# Box_Electronics_v25.net
KiCad netlist of a schematic drawn in EAGLE
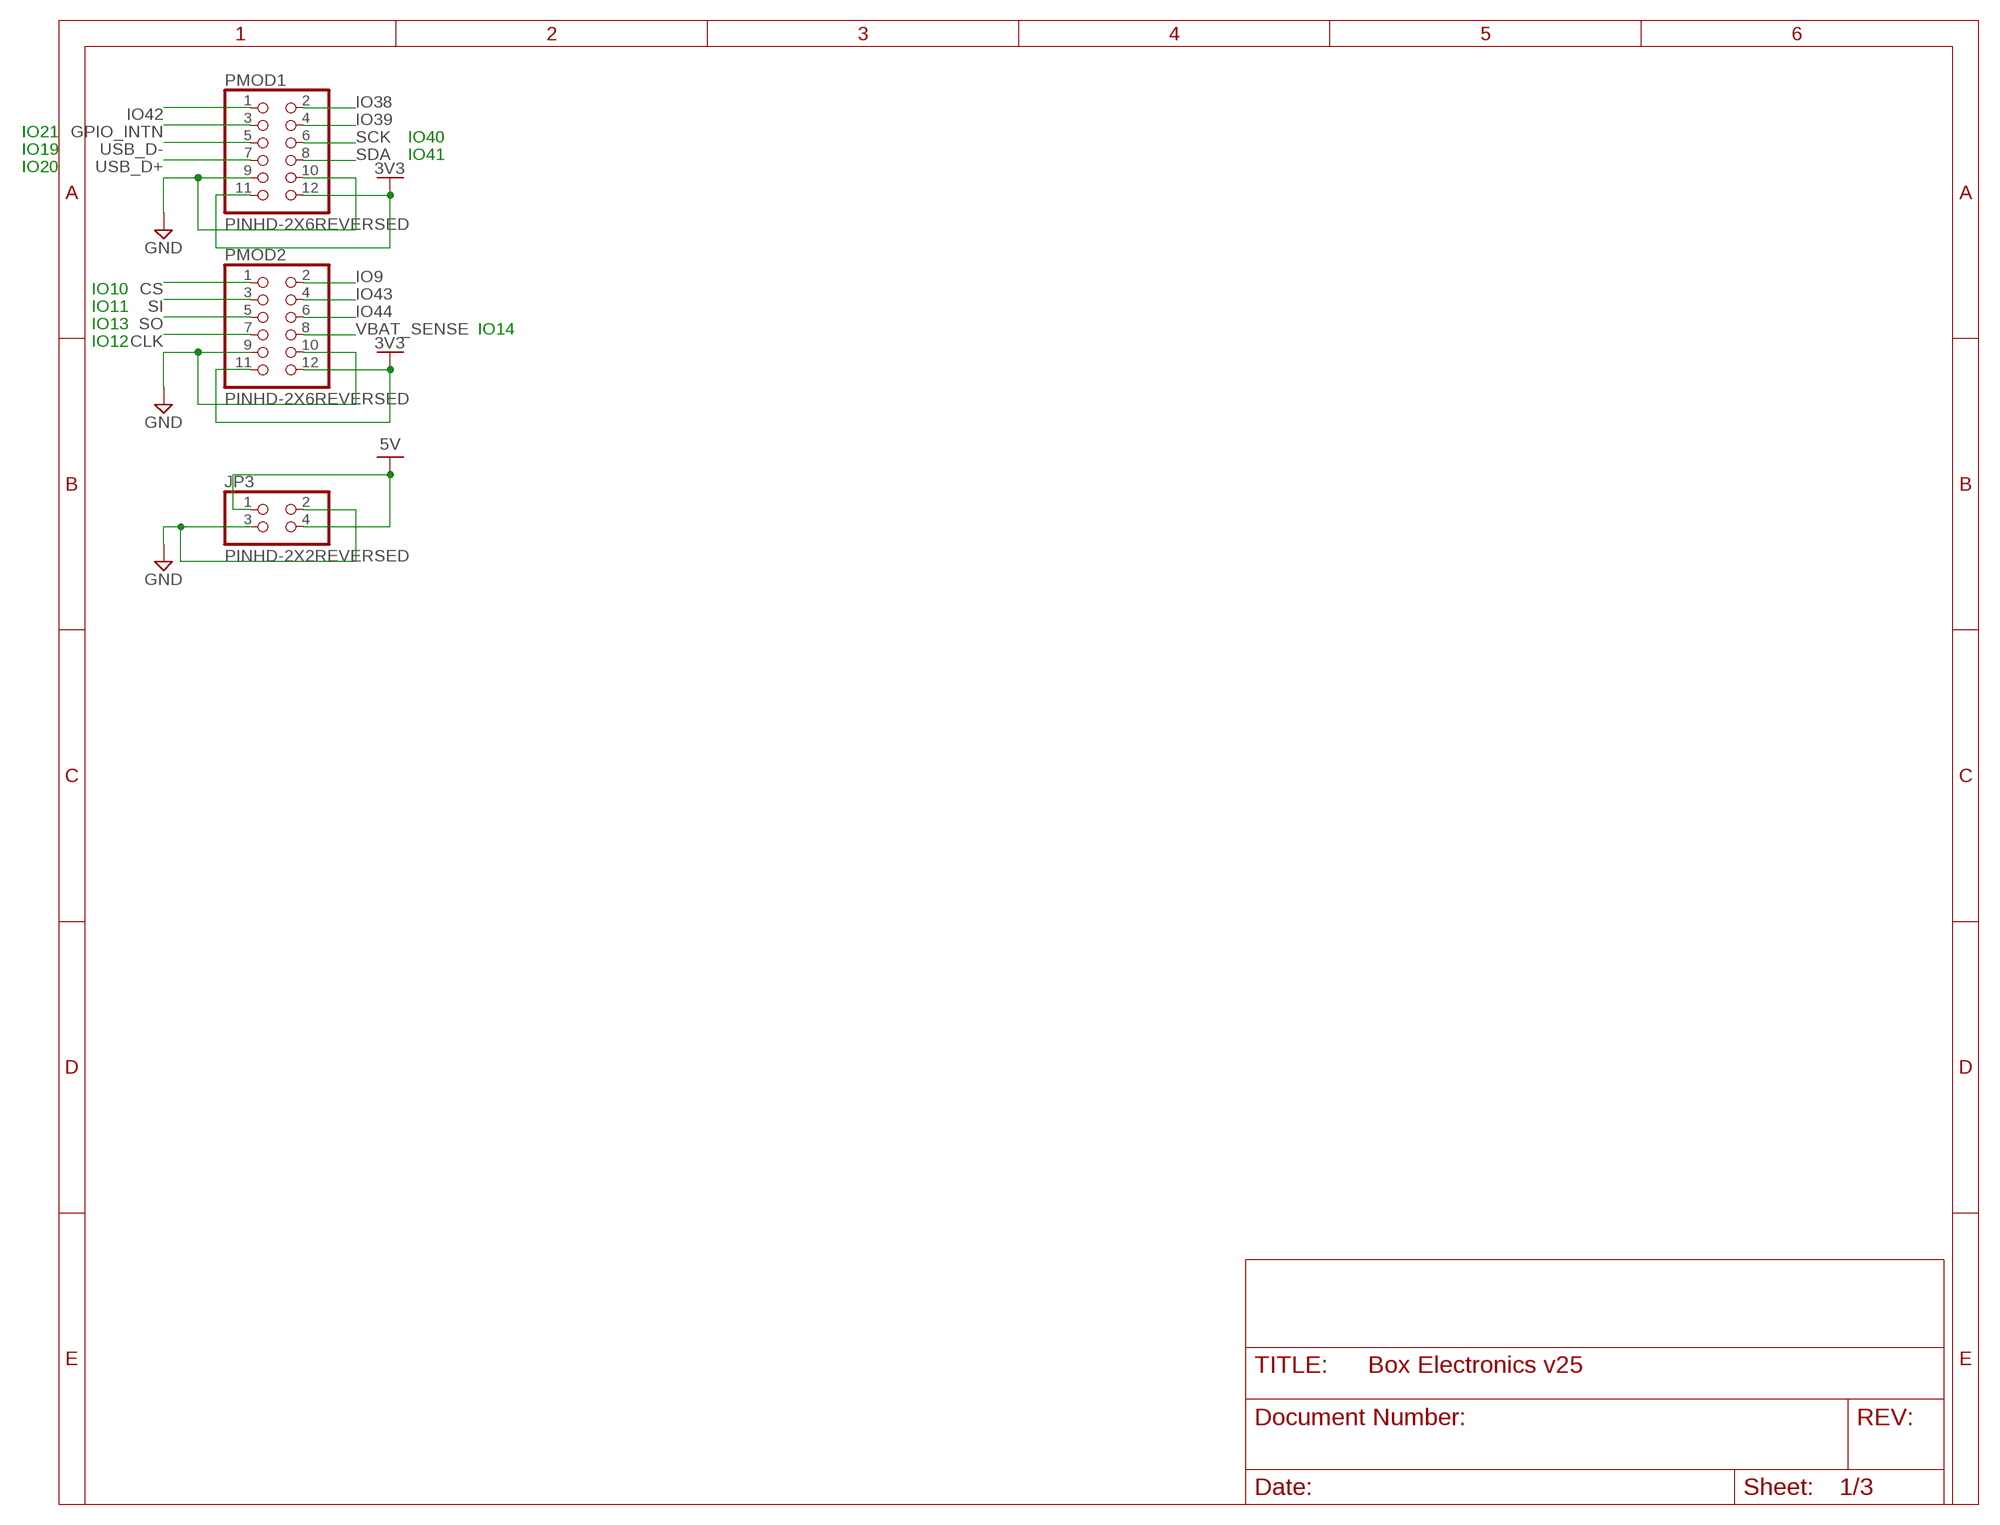
[diagram p0: schematic, sheet 1]
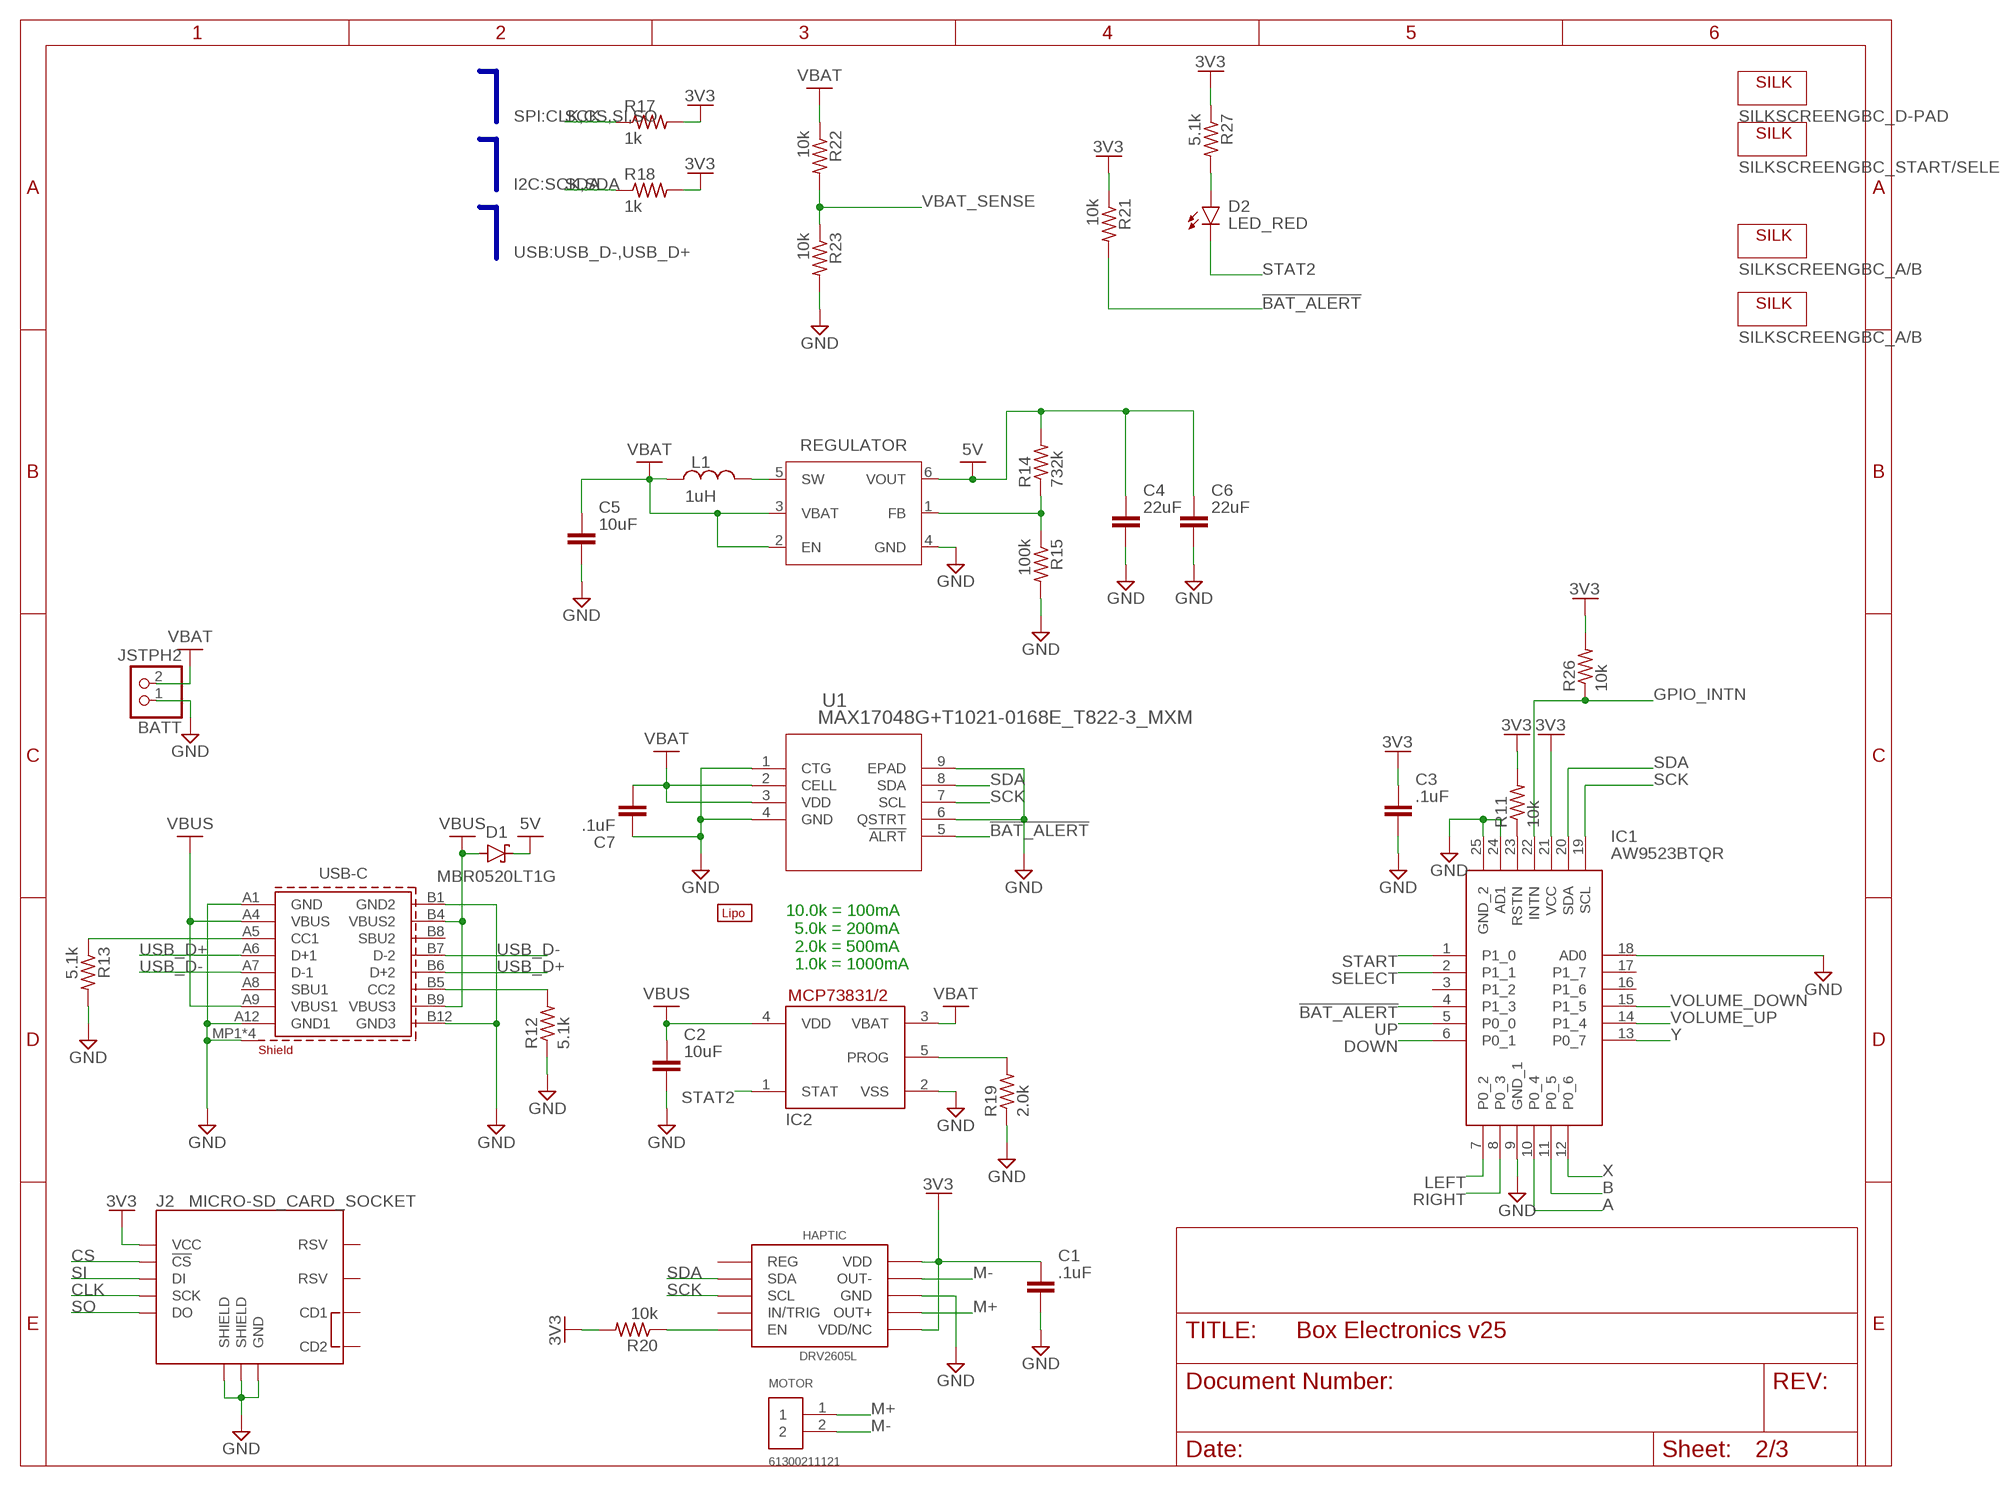
[diagram p1: schematic, sheet 2]
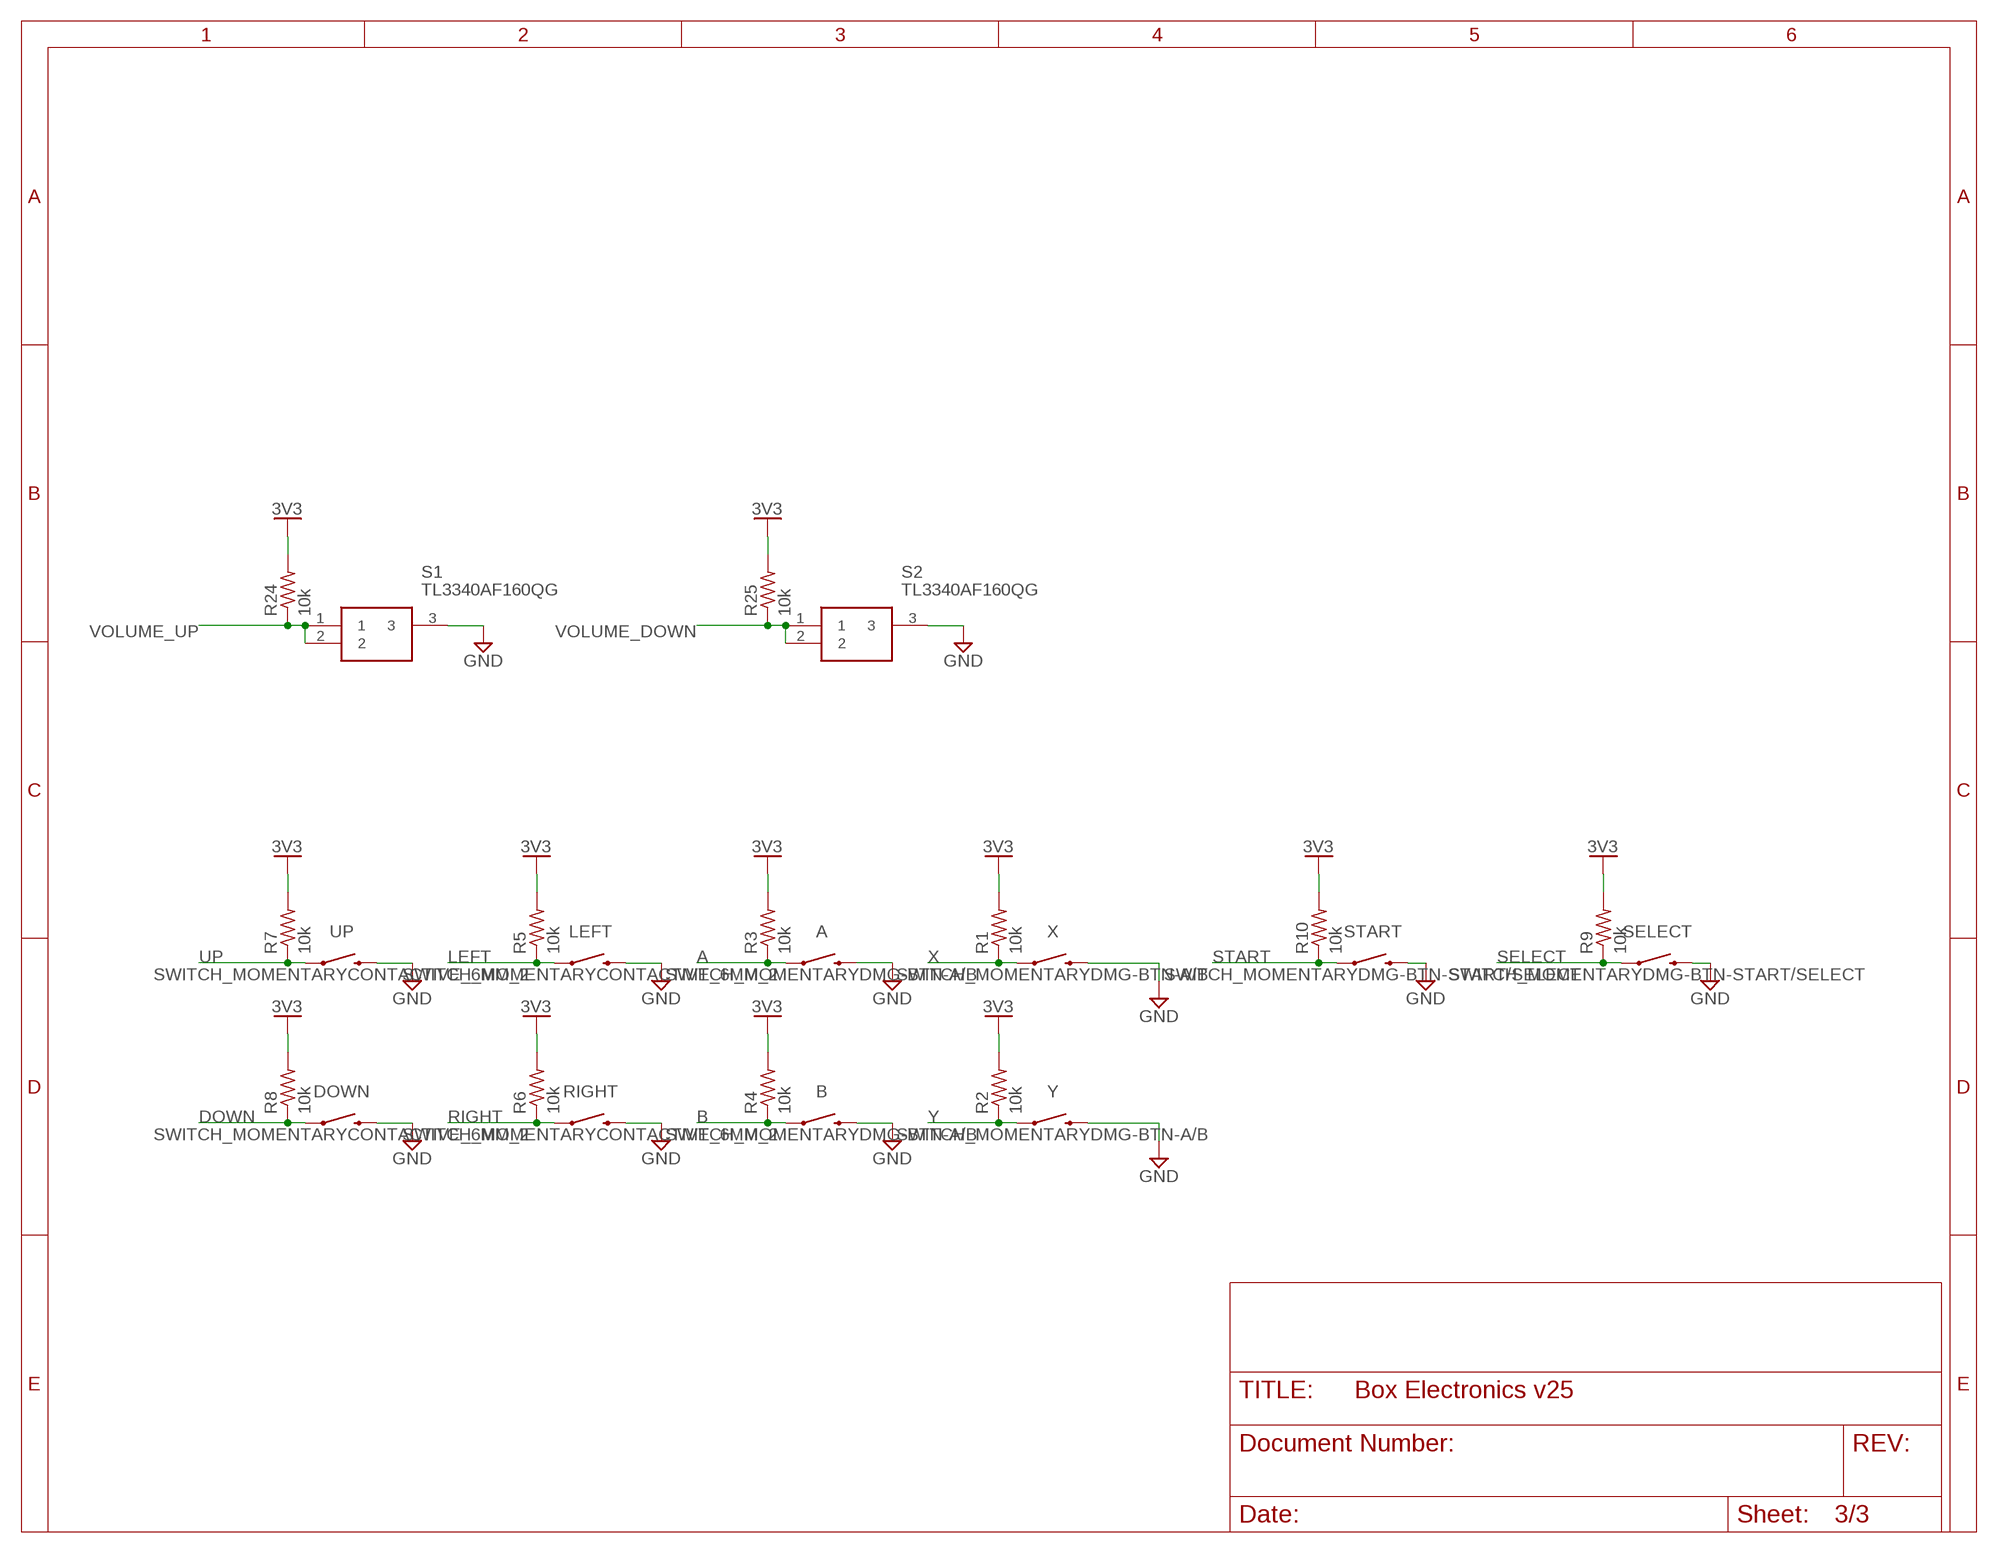
[diagram p2: schematic, sheet 3]

(export (version "E")
  (design (tool "Eeschema 10.0.6"))
  (components
    (comp (ref "A")
      (value "SWITCH_MOMENTARYDMG-BTN-A/B")
      (footprint "eagle-import:DMG_BTN3")
      (libsource (lib "eagle-import") (part "SWITCH_MOMENTARYDMG-BTN-A/B"))
    )
    (comp (ref "B")
      (value "SWITCH_MOMENTARYDMG-BTN-A/B")
      (footprint "eagle-import:DMG_BTN3")
      (libsource (lib "eagle-import") (part "SWITCH_MOMENTARYDMG-BTN-A/B"))
    )
    (comp (ref "DOWN")
      (value "SWITCH_MOMENTARYCONTACTIVE_6MM_2")
      (footprint "eagle-import:BUTTON-CONDUCTIVE_6MM_2")
      (libsource (lib "eagle-import") (part "SWITCH_MOMENTARYCONTACTIVE_6MM_2"))
    )
    (comp (ref "LEFT")
      (value "SWITCH_MOMENTARYCONTACTIVE_6MM_2")
      (footprint "eagle-import:BUTTON-CONDUCTIVE_6MM_2")
      (libsource (lib "eagle-import") (part "SWITCH_MOMENTARYCONTACTIVE_6MM_2"))
    )
    (comp (ref "R1")
      (value "10k")
      (footprint "eagle-import:RESC1608X60")
      (libsource (lib "eagle-import") (part "R-USCHIP-0603(1608-METRIC)_"))
    )
    (comp (ref "R2")
      (value "10k")
      (footprint "eagle-import:RESC1608X60")
      (libsource (lib "eagle-import") (part "R-USCHIP-0603(1608-METRIC)_"))
    )
    (comp (ref "R3")
      (value "10k")
      (footprint "eagle-import:RESC1608X60")
      (libsource (lib "eagle-import") (part "R-USCHIP-0603(1608-METRIC)_"))
    )
    (comp (ref "R4")
      (value "10k")
      (footprint "eagle-import:RESC1608X60")
      (libsource (lib "eagle-import") (part "R-USCHIP-0603(1608-METRIC)_"))
    )
    (comp (ref "R5")
      (value "10k")
      (footprint "eagle-import:RESC1608X60")
      (libsource (lib "eagle-import") (part "R-USCHIP-0603(1608-METRIC)_"))
    )
    (comp (ref "R6")
      (value "10k")
      (footprint "eagle-import:RESC1608X60")
      (libsource (lib "eagle-import") (part "R-USCHIP-0603(1608-METRIC)_"))
    )
    (comp (ref "R7")
      (value "10k")
      (footprint "eagle-import:RESC1608X60")
      (libsource (lib "eagle-import") (part "R-USCHIP-0603(1608-METRIC)_"))
    )
    (comp (ref "R8")
      (value "10k")
      (footprint "eagle-import:RESC1608X60")
      (libsource (lib "eagle-import") (part "R-USCHIP-0603(1608-METRIC)_"))
    )
    (comp (ref "R9")
      (value "10k")
      (footprint "eagle-import:RESC1608X60")
      (libsource (lib "eagle-import") (part "R-USCHIP-0603(1608-METRIC)_"))
    )
    (comp (ref "R10")
      (value "10k")
      (footprint "eagle-import:RESC1608X60")
      (libsource (lib "eagle-import") (part "R-USCHIP-0603(1608-METRIC)_"))
    )
    (comp (ref "R24")
      (value "10k")
      (footprint "eagle-import:RESC1608X60")
      (libsource (lib "eagle-import") (part "R-USCHIP-0603(1608-METRIC)_"))
    )
    (comp (ref "R25")
      (value "10k")
      (footprint "eagle-import:RESC1608X60")
      (libsource (lib "eagle-import") (part "R-USCHIP-0603(1608-METRIC)_"))
    )
    (comp (ref "RIGHT")
      (value "SWITCH_MOMENTARYCONTACTIVE_6MM_2")
      (footprint "eagle-import:BUTTON-CONDUCTIVE_6MM_2")
      (libsource (lib "eagle-import") (part "SWITCH_MOMENTARYCONTACTIVE_6MM_2"))
    )
    (comp (ref "S1")
      (value "TL3340AF160QG")
      (footprint "eagle-import:TL3340")
      (fields (field (name "MOUSER_PART_NUMBER") "612-TL3340AF160QG"))
      (libsource (lib "eagle-import") (part "TL3340AF160QG"))
    )
    (comp (ref "S2")
      (value "TL3340AF160QG")
      (footprint "eagle-import:TL3340")
      (fields (field (name "MOUSER_PART_NUMBER") "612-TL3340AF160QG"))
      (libsource (lib "eagle-import") (part "TL3340AF160QG"))
    )
    (comp (ref "SELECT")
      (value "SWITCH_MOMENTARYDMG-BTN-START/SELECT")
      (footprint "eagle-import:DMG_BTN1_W2")
      (libsource (lib "eagle-import") (part "SWITCH_MOMENTARYDMG-BTN-START/SELECT"))
    )
    (comp (ref "START")
      (value "SWITCH_MOMENTARYDMG-BTN-START/SELECT")
      (footprint "eagle-import:DMG_BTN1_W2")
      (libsource (lib "eagle-import") (part "SWITCH_MOMENTARYDMG-BTN-START/SELECT"))
    )
    (comp (ref "UP")
      (value "SWITCH_MOMENTARYCONTACTIVE_6MM_2")
      (footprint "eagle-import:BUTTON-CONDUCTIVE_6MM_2")
      (libsource (lib "eagle-import") (part "SWITCH_MOMENTARYCONTACTIVE_6MM_2"))
    )
    (comp (ref "X")
      (value "SWITCH_MOMENTARYDMG-BTN-A/B")
      (footprint "eagle-import:DMG_BTN3")
      (libsource (lib "eagle-import") (part "SWITCH_MOMENTARYDMG-BTN-A/B"))
    )
    (comp (ref "Y")
      (value "SWITCH_MOMENTARYDMG-BTN-A/B")
      (footprint "eagle-import:DMG_BTN3")
      (libsource (lib "eagle-import") (part "SWITCH_MOMENTARYDMG-BTN-A/B"))
    )
    (comp (ref "JP3")
      (value "PINHD-2X2REVERSED")
      (footprint "eagle-import:2X02_EDGE_REVERSED")
      (libsource (lib "eagle-import") (part "PINHD-2X2REVERSED"))
    )
    (comp (ref "PMOD1")
      (value "PINHD-2X6REVERSED")
      (footprint "eagle-import:2X06_EDGE_REVERSED")
      (libsource (lib "eagle-import") (part "PINHD-2X6REVERSED"))
    )
    (comp (ref "PMOD2")
      (value "PINHD-2X6REVERSED")
      (footprint "eagle-import:2X06_EDGE_REVERSED")
      (libsource (lib "eagle-import") (part "PINHD-2X6REVERSED"))
    )
    (comp (ref "BATT")
      (value "JSTPH2")
      (footprint "eagle-import:JSTPH2")
      (libsource (lib "eagle-import") (part "JSTPH2"))
    )
    (comp (ref "BT1")
      (value "LIPO-OUTLINE1100")
      (footprint "eagle-import:LIPO-1000")
      (libsource (lib "eagle-import") (part "LIPO-OUTLINE1100"))
    )
    (comp (ref "C1")
      (value ".1uF")
      (footprint "eagle-import:CAPC1608X85")
      (libsource (lib "eagle-import") (part "CCHIP-0603(1608-METRIC)_"))
    )
    (comp (ref "C2")
      (value "10uF")
      (footprint "eagle-import:CAPC1608X85")
      (libsource (lib "eagle-import") (part "CCHIP-0603(1608-METRIC)_"))
    )
    (comp (ref "C3")
      (value ".1uF")
      (footprint "eagle-import:CAPC1608X85")
      (libsource (lib "eagle-import") (part "CCHIP-0603(1608-METRIC)_"))
    )
    (comp (ref "C4")
      (value "22uF")
      (footprint "eagle-import:CAPC2012X110")
      (libsource (lib "eagle-import") (part "CCHIP-0805(2012-METRIC)_"))
    )
    (comp (ref "C5")
      (value "10uF")
      (footprint "eagle-import:CAPC1608X85")
      (libsource (lib "eagle-import") (part "CCHIP-0603(1608-METRIC)_"))
    )
    (comp (ref "C6")
      (value "22uF")
      (footprint "eagle-import:CAPC2012X110")
      (libsource (lib "eagle-import") (part "CCHIP-0805(2012-METRIC)_"))
    )
    (comp (ref "C7")
      (value ".1uF")
      (footprint "eagle-import:CAPC1608X85")
      (libsource (lib "eagle-import") (part "CCHIP-0603(1608-METRIC)_"))
    )
    (comp (ref "D1")
      (value "MBR0520LT1G")
      (footprint "eagle-import:SODFL3718X115")
      (fields (field (name "MANUFACTURER") "ON Semiconductor"))
      (libsource (lib "eagle-import") (part "SCHOTTKY_DO-219MBR0520LT1G"))
    )
    (comp (ref "D2")
      (value "LED_RED")
      (footprint "eagle-import:LEDC2012X110N_FLAT-R")
      (libsource (lib "eagle-import") (part "CHIP-FLAT-R_0805"))
    )
    (comp (ref "HAPTIC")
      (value "DRV2605L")
      (footprint "eagle-import:VSSOP-10")
      (libsource (lib "eagle-import") (part "DRV2605L"))
    )
    (comp (ref "IC1")
      (value "AW9523BTQR")
      (footprint "eagle-import:QFN50P400X400X80-25N")
      (libsource (lib "eagle-import") (part "AW9523BTQR"))
    )
    (comp (ref "IC2")
      (value "MCP73831/OT")
      (footprint "eagle-import:SOT23-5L")
      (libsource (lib "eagle-import") (part "MCP73831/OT"))
    )
    (comp (ref "J2")
      (value "MICRO-SD_CARD_SOCKET")
      (footprint "eagle-import:MICRO-SD-SOCKET")
      (libsource (lib "eagle-import") (part "MICRO-SD_CARD_SOCKET"))
    )
    (comp (ref "L1")
      (value "1uH")
      (footprint "eagle-import:INDC2009X120")
      (libsource (lib "eagle-import") (part "LCHIP-0805(2012-METRIC)_"))
    )
    (comp (ref "MOTOR")
      (value "61300211121")
      (footprint "eagle-import:61300211121")
      (fields
        (field (name "DIGI_KEY_PART_NUMBER") "732-5315-ND")
        (field (name "MANUFACTURER") "Wurth Electronics Inc.")
        (field (name "CREATED_BY") "PCBLayout.com")
      )
      (libsource (lib "eagle-import") (part "61300211121"))
    )
    (comp (ref "R11")
      (value "10k")
      (footprint "eagle-import:RESC1608X60")
      (libsource (lib "eagle-import") (part "R-USCHIP-0603(1608-METRIC)_"))
    )
    (comp (ref "R12")
      (value "5.1k")
      (footprint "eagle-import:RESC1608X60")
      (libsource (lib "eagle-import") (part "R-USCHIP-0603(1608-METRIC)_"))
    )
    (comp (ref "R13")
      (value "5.1k")
      (footprint "eagle-import:RESC1608X60")
      (libsource (lib "eagle-import") (part "R-USCHIP-0603(1608-METRIC)_"))
    )
    (comp (ref "R14")
      (value "732k")
      (footprint "eagle-import:RESC1608X60")
      (libsource (lib "eagle-import") (part "R-USCHIP-0603(1608-METRIC)_"))
    )
    (comp (ref "R15")
      (value "100k")
      (footprint "eagle-import:RESC1608X60")
      (libsource (lib "eagle-import") (part "R-USCHIP-0603(1608-METRIC)_"))
    )
    (comp (ref "R17")
      (value "1k")
      (footprint "eagle-import:RESC1608X60")
      (libsource (lib "eagle-import") (part "R-USCHIP-0603(1608-METRIC)_"))
    )
    (comp (ref "R18")
      (value "1k")
      (footprint "eagle-import:RESC1608X60")
      (libsource (lib "eagle-import") (part "R-USCHIP-0603(1608-METRIC)_"))
    )
    (comp (ref "R19")
      (value "2.0k")
      (footprint "eagle-import:RESC1608X60")
      (libsource (lib "eagle-import") (part "R-USCHIP-0603(1608-METRIC)_"))
    )
    (comp (ref "R20")
      (value "10k")
      (footprint "eagle-import:RESC1608X60")
      (libsource (lib "eagle-import") (part "R-USCHIP-0603(1608-METRIC)_"))
    )
    (comp (ref "R21")
      (value "10k")
      (footprint "eagle-import:RESC1608X60")
      (libsource (lib "eagle-import") (part "R-USCHIP-0603(1608-METRIC)_"))
    )
    (comp (ref "R22")
      (value "10k")
      (footprint "eagle-import:RESC1608X60")
      (libsource (lib "eagle-import") (part "R-USCHIP-0603(1608-METRIC)_"))
    )
    (comp (ref "R23")
      (value "10k")
      (footprint "eagle-import:RESC1608X60")
      (libsource (lib "eagle-import") (part "R-USCHIP-0603(1608-METRIC)_"))
    )
    (comp (ref "R26")
      (value "10k")
      (footprint "eagle-import:RESC1608X60")
      (libsource (lib "eagle-import") (part "R-USCHIP-0603(1608-METRIC)_"))
    )
    (comp (ref "R27")
      (value "5.1k")
      (footprint "eagle-import:RESC1608X60")
      (libsource (lib "eagle-import") (part "R-USCHIP-0603(1608-METRIC)_"))
    )
    (comp (ref "REGULATOR")
      (value "TPS61070")
      (footprint "eagle-import:SOT563")
      (libsource (lib "eagle-import") (part "TPS61023"))
    )
    (comp (ref "U$1")
      (value "SILKSCREENGBC_D-PAD")
      (footprint "eagle-import:GAMEBOY_COLOR_DPAD_SILK")
      (libsource (lib "eagle-import") (part "SILKSCREENGBC_D-PAD"))
    )
    (comp (ref "U$2")
      (value "SILKSCREENGBC_START/SELECT")
      (footprint "eagle-import:GAMEBOY_COLOR_START_SELECT_SILK")
      (libsource (lib "eagle-import") (part "SILKSCREENGBC_START/SELECT"))
    )
    (comp (ref "U$3")
      (value "SILKSCREENGBC_A/B")
      (footprint "eagle-import:GAMEBOY_COLOR_A_B_BUTTON_MEMBRANE")
      (libsource (lib "eagle-import") (part "SILKSCREENGBC_A/B"))
    )
    (comp (ref "U$4")
      (value "SILKSCREENGBC_A/B")
      (footprint "eagle-import:GAMEBOY_COLOR_A_B_BUTTON_MEMBRANE")
      (libsource (lib "eagle-import") (part "SILKSCREENGBC_A/B"))
    )
    (comp (ref "U1")
      (value "MAX17048G+T1021-0168E_T822-3_MXM")
      (footprint "eagle-import:21-0168E_T822-3_MXM")
      (fields
        (field (name "MANUFACTURER_PART_NUMBER") "MAX17048G+T10")
        (field (name "COPYRIGHT") "Copyright (C) 2023 Ultra Librarian. All rights reserved.")
      )
      (libsource (lib "eagle-import") (part "MAX17048G+T1021-0168E_T822-3_MXM"))
    )
    (comp (ref "USB-C")
      (value "629722000214")
      (footprint "eagle-import:USB4110GFA")
      (libsource (lib "eagle-import") (part "629722000214SMD"))
    )
  )
  (nets
    (net (code "7") (name "3V3") (class "Default")
      (node (ref "C1") (pin "1") (pinfunction "1_1") (pintype "passive"))
      (node (ref "C3") (pin "1") (pinfunction "1_1") (pintype "passive"))
      (node (ref "HAPTIC") (pin "P$10") (pinfunction "VDD_P$10") (pintype "bidirectional"))
      (node (ref "HAPTIC") (pin "P$6") (pinfunction "VDD/NC_P$6") (pintype "bidirectional"))
      (node (ref "IC1") (pin "21") (pinfunction "VCC_21") (pintype "bidirectional"))
      (node (ref "J2") (pin "VCC") (pinfunction "VCC_VCC") (pintype "bidirectional"))
      (node (ref "PMOD1") (pin "11") (pinfunction "11_11") (pintype "passive"))
      (node (ref "PMOD1") (pin "12") (pinfunction "12_12") (pintype "passive"))
      (node (ref "PMOD2") (pin "11") (pinfunction "11_11") (pintype "passive"))
      (node (ref "PMOD2") (pin "12") (pinfunction "12_12") (pintype "passive"))
      (node (ref "R1") (pin "2") (pinfunction "2_2") (pintype "passive"))
      (node (ref "R10") (pin "2") (pinfunction "2_2") (pintype "passive"))
      (node (ref "R11") (pin "2") (pinfunction "2_2") (pintype "passive"))
      (node (ref "R17") (pin "2") (pinfunction "2_2") (pintype "passive"))
      (node (ref "R18") (pin "2") (pinfunction "2_2") (pintype "passive"))
      (node (ref "R2") (pin "2") (pinfunction "2_2") (pintype "passive"))
      (node (ref "R20") (pin "2") (pinfunction "2_2") (pintype "passive"))
      (node (ref "R21") (pin "1") (pinfunction "1_1") (pintype "passive"))
      (node (ref "R24") (pin "2") (pinfunction "2_2") (pintype "passive"))
      (node (ref "R25") (pin "2") (pinfunction "2_2") (pintype "passive"))
      (node (ref "R26") (pin "2") (pinfunction "2_2") (pintype "passive"))
      (node (ref "R27") (pin "1") (pinfunction "1_1") (pintype "passive"))
      (node (ref "R3") (pin "2") (pinfunction "2_2") (pintype "passive"))
      (node (ref "R4") (pin "2") (pinfunction "2_2") (pintype "passive"))
      (node (ref "R5") (pin "2") (pinfunction "2_2") (pintype "passive"))
      (node (ref "R6") (pin "2") (pinfunction "2_2") (pintype "passive"))
      (node (ref "R7") (pin "2") (pinfunction "2_2") (pintype "passive"))
      (node (ref "R8") (pin "2") (pinfunction "2_2") (pintype "passive"))
      (node (ref "R9") (pin "2") (pinfunction "2_2") (pintype "passive"))
    )
    (net (code "8") (name "5V") (class "Default")
      (node (ref "C4") (pin "1") (pinfunction "1_1") (pintype "passive"))
      (node (ref "C6") (pin "1") (pinfunction "1_1") (pintype "passive"))
      (node (ref "D1") (pin "1") (pinfunction "C_1") (pintype "passive"))
      (node (ref "JP3") (pin "1") (pinfunction "1_1") (pintype "passive"))
      (node (ref "JP3") (pin "4") (pinfunction "4_4") (pintype "passive"))
      (node (ref "R14") (pin "2") (pinfunction "2_2") (pintype "passive"))
      (node (ref "REGULATOR") (pin "6") (pinfunction "VOUT_6") (pintype "output"))
    )
    (net (code "9") (name "A") (class "Default")
      (node (ref "A") (pin "P$1") (pinfunction "1_P$1") (pintype "passive"))
      (node (ref "A") (pin "P$3") (pinfunction "1_P$3") (pintype "passive"))
      (node (ref "IC1") (pin "10") (pinfunction "P0_4_10") (pintype "bidirectional"))
      (node (ref "R3") (pin "1") (pinfunction "1_1") (pintype "passive"))
    )
    (net (code "10") (name "B") (class "Default")
      (node (ref "B") (pin "P$1") (pinfunction "1_P$1") (pintype "passive"))
      (node (ref "B") (pin "P$3") (pinfunction "1_P$3") (pintype "passive"))
      (node (ref "IC1") (pin "11") (pinfunction "P0_5_11") (pintype "bidirectional"))
      (node (ref "R4") (pin "1") (pinfunction "1_1") (pintype "passive"))
    )
    (net (code "11") (name "CLK") (class "Default")
      (node (ref "J2") (pin "SCLK") (pinfunction "SCK_SCLK") (pintype "bidirectional"))
      (node (ref "PMOD2") (pin "7") (pinfunction "7_7") (pintype "passive"))
    )
    (net (code "12") (name "CS") (class "Default")
      (node (ref "J2") (pin "CS") (pinfunction "~{CS}_CS") (pintype "bidirectional"))
      (node (ref "PMOD2") (pin "1") (pinfunction "1_1") (pintype "passive"))
    )
    (net (code "13") (name "DOWN") (class "Default")
      (node (ref "DOWN") (pin "1") (pinfunction "1_1") (pintype "passive"))
      (node (ref "IC1") (pin "6") (pinfunction "P0_1_6") (pintype "bidirectional"))
      (node (ref "R8") (pin "1") (pinfunction "1_1") (pintype "passive"))
    )
    (net (code "14") (name "GND") (class "Default")
      (node (ref "A") (pin "P$2") (pinfunction "2_P$2") (pintype "passive"))
      (node (ref "A") (pin "P$4") (pinfunction "2_P$4") (pintype "passive"))
      (node (ref "B") (pin "P$2") (pinfunction "2_P$2") (pintype "passive"))
      (node (ref "B") (pin "P$4") (pinfunction "2_P$4") (pintype "passive"))
      (node (ref "BATT") (pin "1") (pinfunction "1_1") (pintype "passive"))
      (node (ref "C1") (pin "2") (pinfunction "2_2") (pintype "passive"))
      (node (ref "C2") (pin "2") (pinfunction "2_2") (pintype "passive"))
      (node (ref "C3") (pin "2") (pinfunction "2_2") (pintype "passive"))
      (node (ref "C4") (pin "2") (pinfunction "2_2") (pintype "passive"))
      (node (ref "C5") (pin "2") (pinfunction "2_2") (pintype "passive"))
      (node (ref "C6") (pin "2") (pinfunction "2_2") (pintype "passive"))
      (node (ref "C7") (pin "1") (pinfunction "1_1") (pintype "passive"))
      (node (ref "DOWN") (pin "2") (pinfunction "2_2") (pintype "passive"))
      (node (ref "HAPTIC") (pin "P$8") (pinfunction "GND_P$8") (pintype "bidirectional"))
      (node (ref "IC1") (pin "18") (pinfunction "AD0_18") (pintype "bidirectional"))
      (node (ref "IC1") (pin "24") (pinfunction "AD1_24") (pintype "bidirectional"))
      (node (ref "IC1") (pin "25") (pinfunction "GND_2_25") (pintype "bidirectional"))
      (node (ref "IC1") (pin "9") (pinfunction "GND_1_9") (pintype "bidirectional"))
      (node (ref "IC2") (pin "2") (pinfunction "VSS_2") (pintype "power_in"))
      (node (ref "J2") (pin "GND") (pinfunction "GND_GND") (pintype "bidirectional"))
      (node (ref "J2") (pin "GND1") (pinfunction "SHIELD_GND1") (pintype "bidirectional"))
      (node (ref "J2") (pin "GND3") (pinfunction "SHIELD_GND3") (pintype "bidirectional"))
      (node (ref "JP3") (pin "2") (pinfunction "2_2") (pintype "passive"))
      (node (ref "JP3") (pin "3") (pinfunction "3_3") (pintype "passive"))
      (node (ref "LEFT") (pin "2") (pinfunction "2_2") (pintype "passive"))
      (node (ref "PMOD1") (pin "10") (pinfunction "10_10") (pintype "passive"))
      (node (ref "PMOD1") (pin "9") (pinfunction "9_9") (pintype "passive"))
      (node (ref "PMOD2") (pin "10") (pinfunction "10_10") (pintype "passive"))
      (node (ref "PMOD2") (pin "9") (pinfunction "9_9") (pintype "passive"))
      (node (ref "R12") (pin "1") (pinfunction "1_1") (pintype "passive"))
      (node (ref "R13") (pin "2") (pinfunction "2_2") (pintype "passive"))
      (node (ref "R15") (pin "2") (pinfunction "2_2") (pintype "passive"))
      (node (ref "R19") (pin "1") (pinfunction "1_1") (pintype "passive"))
      (node (ref "R23") (pin "2") (pinfunction "2_2") (pintype "passive"))
      (node (ref "REGULATOR") (pin "4") (pinfunction "GND_4") (pintype "power_in"))
      (node (ref "RIGHT") (pin "2") (pinfunction "2_2") (pintype "passive"))
      (node (ref "S1") (pin "3") (pinfunction "3_3") (pintype "bidirectional"))
      (node (ref "S2") (pin "3") (pinfunction "3_3") (pintype "bidirectional"))
      (node (ref "SELECT") (pin "P$2") (pinfunction "2_P$2") (pintype "passive"))
      (node (ref "SELECT") (pin "P$4") (pinfunction "2_P$4") (pintype "passive"))
      (node (ref "START") (pin "P$2") (pinfunction "2_P$2") (pintype "passive"))
      (node (ref "START") (pin "P$4") (pinfunction "2_P$4") (pintype "passive"))
      (node (ref "U1") (pin "1") (pinfunction "CTG_1") (pintype "passive"))
      (node (ref "U1") (pin "4") (pinfunction "GND_4") (pintype "power_in"))
      (node (ref "U1") (pin "6") (pinfunction "QSTRT_6") (pintype "input"))
      (node (ref "U1") (pin "9") (pinfunction "EPAD_9") (pintype "passive"))
      (node (ref "UP") (pin "2") (pinfunction "2_2") (pintype "passive"))
      (node (ref "USB-C") (pin "A1") (pinfunction "GND_A1") (pintype "passive"))
      (node (ref "USB-C") (pin "A12") (pinfunction "GND1_A12") (pintype "passive"))
      (node (ref "USB-C") (pin "B1") (pinfunction "GND2_B1") (pintype "passive"))
      (node (ref "USB-C") (pin "B12") (pinfunction "GND3_B12") (pintype "passive"))
      (node (ref "USB-C") (pin "MP1") (pinfunction "SHIELD_MP1") (pintype "passive"))
      (node (ref "USB-C") (pin "MP2") (pinfunction "SHIELD_MP2") (pintype "passive"))
      (node (ref "USB-C") (pin "MP3") (pinfunction "SHIELD_MP3") (pintype "passive"))
      (node (ref "USB-C") (pin "MP4") (pinfunction "SHIELD_MP4") (pintype "passive"))
      (node (ref "X") (pin "P$2") (pinfunction "2_P$2") (pintype "passive"))
      (node (ref "X") (pin "P$4") (pinfunction "2_P$4") (pintype "passive"))
      (node (ref "Y") (pin "P$2") (pinfunction "2_P$2") (pintype "passive"))
      (node (ref "Y") (pin "P$4") (pinfunction "2_P$4") (pintype "passive"))
    )
    (net (code "15") (name "GPIO_INTN") (class "Default")
      (node (ref "IC1") (pin "22") (pinfunction "INTN_22") (pintype "bidirectional"))
      (node (ref "PMOD1") (pin "3") (pinfunction "3_3") (pintype "passive"))
      (node (ref "R26") (pin "1") (pinfunction "1_1") (pintype "passive"))
    )
    (net (code "16") (name "IO9") (class "Default")
      (node (ref "PMOD2") (pin "2") (pinfunction "2_2") (pintype "passive"))
    )
    (net (code "17") (name "IO38") (class "Default")
      (node (ref "PMOD1") (pin "2") (pinfunction "2_2") (pintype "passive"))
    )
    (net (code "18") (name "IO39") (class "Default")
      (node (ref "PMOD1") (pin "4") (pinfunction "4_4") (pintype "passive"))
    )
    (net (code "19") (name "IO42") (class "Default")
      (node (ref "PMOD1") (pin "1") (pinfunction "1_1") (pintype "passive"))
    )
    (net (code "20") (name "IO43") (class "Default")
      (node (ref "PMOD2") (pin "4") (pinfunction "4_4") (pintype "passive"))
    )
    (net (code "21") (name "IO44") (class "Default")
      (node (ref "PMOD2") (pin "6") (pinfunction "6_6") (pintype "passive"))
    )
    (net (code "22") (name "LEFT") (class "Default")
      (node (ref "IC1") (pin "7") (pinfunction "P0_2_7") (pintype "bidirectional"))
      (node (ref "LEFT") (pin "1") (pinfunction "1_1") (pintype "passive"))
      (node (ref "R5") (pin "1") (pinfunction "1_1") (pintype "passive"))
    )
    (net (code "23") (name "M+") (class "Default")
      (node (ref "HAPTIC") (pin "P$7") (pinfunction "OUT+_P$7") (pintype "bidirectional"))
      (node (ref "MOTOR") (pin "1") (pinfunction "1_1") (pintype "passive"))
    )
    (net (code "24") (name "M-") (class "Default")
      (node (ref "HAPTIC") (pin "P$9") (pinfunction "OUT-_P$9") (pintype "bidirectional"))
      (node (ref "MOTOR") (pin "2") (pinfunction "2_2") (pintype "passive"))
    )
    (net (code "25") (name "Net-(D2-PadA)") (class "Default")
      (node (ref "D2") (pin "A") (pinfunction "A_A") (pintype "passive"))
      (node (ref "R27") (pin "2") (pinfunction "2_2") (pintype "passive"))
    )
    (net (code "26") (name "Net-(HAPTIC-EN)") (class "Default")
      (node (ref "HAPTIC") (pin "P$5") (pinfunction "EN_P$5") (pintype "bidirectional"))
      (node (ref "R20") (pin "1") (pinfunction "1_1") (pintype "passive"))
    )
    (net (code "27") (name "Net-(IC1-RSTN)") (class "Default")
      (node (ref "IC1") (pin "23") (pinfunction "RSTN_23") (pintype "bidirectional"))
      (node (ref "R11") (pin "1") (pinfunction "1_1") (pintype "passive"))
    )
    (net (code "28") (name "Net-(IC2-PROG)") (class "Default")
      (node (ref "IC2") (pin "5") (pinfunction "PROG_5") (pintype "input"))
      (node (ref "R19") (pin "2") (pinfunction "2_2") (pintype "passive"))
    )
    (net (code "29") (name "Net-(REGULATOR-FB)") (class "Default")
      (node (ref "R14") (pin "1") (pinfunction "1_1") (pintype "passive"))
      (node (ref "R15") (pin "1") (pinfunction "1_1") (pintype "passive"))
      (node (ref "REGULATOR") (pin "1") (pinfunction "FB_1") (pintype "input"))
    )
    (net (code "30") (name "Net-(REGULATOR-SW)") (class "Default")
      (node (ref "L1") (pin "2") (pinfunction "2_2") (pintype "passive"))
      (node (ref "REGULATOR") (pin "5") (pinfunction "SW_5") (pintype "input"))
    )
    (net (code "31") (name "Net-(USB-C-CC1)") (class "Default")
      (node (ref "R13") (pin "1") (pinfunction "1_1") (pintype "passive"))
      (node (ref "USB-C") (pin "A5") (pinfunction "CC1_A5") (pintype "passive"))
    )
    (net (code "32") (name "Net-(USB-C-CC2)") (class "Default")
      (node (ref "R12") (pin "2") (pinfunction "2_2") (pintype "passive"))
      (node (ref "USB-C") (pin "B5") (pinfunction "CC2_B5") (pintype "passive"))
    )
    (net (code "33") (name "RIGHT") (class "Default")
      (node (ref "IC1") (pin "8") (pinfunction "P0_3_8") (pintype "bidirectional"))
      (node (ref "R6") (pin "1") (pinfunction "1_1") (pintype "passive"))
      (node (ref "RIGHT") (pin "1") (pinfunction "1_1") (pintype "passive"))
    )
    (net (code "34") (name "SCK") (class "Default")
      (node (ref "HAPTIC") (pin "P$2") (pinfunction "SCL_P$2") (pintype "bidirectional"))
      (node (ref "IC1") (pin "19") (pinfunction "SCL_19") (pintype "bidirectional"))
      (node (ref "PMOD1") (pin "6") (pinfunction "6_6") (pintype "passive"))
      (node (ref "R17") (pin "1") (pinfunction "1_1") (pintype "passive"))
      (node (ref "U1") (pin "7") (pinfunction "SCL_7") (pintype "input"))
    )
    (net (code "35") (name "SDA") (class "Default")
      (node (ref "HAPTIC") (pin "P$3") (pinfunction "SDA_P$3") (pintype "bidirectional"))
      (node (ref "IC1") (pin "20") (pinfunction "SDA_20") (pintype "bidirectional"))
      (node (ref "PMOD1") (pin "8") (pinfunction "8_8") (pintype "passive"))
      (node (ref "R18") (pin "1") (pinfunction "1_1") (pintype "passive"))
      (node (ref "U1") (pin "8") (pinfunction "SDA_8") (pintype "bidirectional"))
    )
    (net (code "36") (name "SELECT") (class "Default")
      (node (ref "IC1") (pin "2") (pinfunction "P1_1_2") (pintype "bidirectional"))
      (node (ref "R9") (pin "1") (pinfunction "1_1") (pintype "passive"))
      (node (ref "SELECT") (pin "P$1") (pinfunction "1_P$1") (pintype "passive"))
      (node (ref "SELECT") (pin "P$3") (pinfunction "1_P$3") (pintype "passive"))
    )
    (net (code "37") (name "SI") (class "Default")
      (node (ref "J2") (pin "DI") (pinfunction "DI_DI") (pintype "bidirectional"))
      (node (ref "PMOD2") (pin "3") (pinfunction "3_3") (pintype "passive"))
    )
    (net (code "38") (name "SO") (class "Default")
      (node (ref "J2") (pin "DO") (pinfunction "DO_DO") (pintype "bidirectional"))
      (node (ref "PMOD2") (pin "5") (pinfunction "5_5") (pintype "passive"))
    )
    (net (code "39") (name "START") (class "Default")
      (node (ref "IC1") (pin "1") (pinfunction "P1_0_1") (pintype "bidirectional"))
      (node (ref "R10") (pin "1") (pinfunction "1_1") (pintype "passive"))
      (node (ref "START") (pin "P$1") (pinfunction "1_P$1") (pintype "passive"))
      (node (ref "START") (pin "P$3") (pinfunction "1_P$3") (pintype "passive"))
    )
    (net (code "40") (name "STAT2") (class "Default")
      (node (ref "D2") (pin "C") (pinfunction "C_C") (pintype "passive"))
      (node (ref "IC2") (pin "1") (pinfunction "STAT_1") (pintype "output"))
    )
    (net (code "41") (name "UP") (class "Default")
      (node (ref "IC1") (pin "5") (pinfunction "P0_0_5") (pintype "bidirectional"))
      (node (ref "R7") (pin "1") (pinfunction "1_1") (pintype "passive"))
      (node (ref "UP") (pin "1") (pinfunction "1_1") (pintype "passive"))
    )
    (net (code "42") (name "USB_D+") (class "Default")
      (node (ref "PMOD1") (pin "7") (pinfunction "7_7") (pintype "passive"))
      (node (ref "USB-C") (pin "A6") (pinfunction "D+1_A6") (pintype "passive"))
      (node (ref "USB-C") (pin "B6") (pinfunction "D+2_B6") (pintype "passive"))
    )
    (net (code "43") (name "USB_D-") (class "Default")
      (node (ref "PMOD1") (pin "5") (pinfunction "5_5") (pintype "passive"))
      (node (ref "USB-C") (pin "A7") (pinfunction "D-1_A7") (pintype "passive"))
      (node (ref "USB-C") (pin "B7") (pinfunction "D-2_B7") (pintype "passive"))
    )
    (net (code "44") (name "VBAT") (class "Default")
      (node (ref "BATT") (pin "2") (pinfunction "2_2") (pintype "passive"))
      (node (ref "C5") (pin "1") (pinfunction "1_1") (pintype "passive"))
      (node (ref "C7") (pin "2") (pinfunction "2_2") (pintype "passive"))
      (node (ref "IC2") (pin "3") (pinfunction "VBAT_3") (pintype "bidirectional"))
      (node (ref "L1") (pin "1") (pinfunction "1_1") (pintype "passive"))
      (node (ref "R22") (pin "1") (pinfunction "1_1") (pintype "passive"))
      (node (ref "REGULATOR") (pin "2") (pinfunction "EN_2") (pintype "input"))
      (node (ref "REGULATOR") (pin "3") (pinfunction "VBAT_3") (pintype "input"))
      (node (ref "U1") (pin "2") (pinfunction "CELL_2") (pintype "passive"))
      (node (ref "U1") (pin "3") (pinfunction "VDD_3") (pintype "power_in"))
    )
    (net (code "45") (name "VBAT_SENSE") (class "Default")
      (node (ref "PMOD2") (pin "8") (pinfunction "8_8") (pintype "passive"))
      (node (ref "R22") (pin "2") (pinfunction "2_2") (pintype "passive"))
      (node (ref "R23") (pin "1") (pinfunction "1_1") (pintype "passive"))
    )
    (net (code "46") (name "VBUS") (class "Default")
      (node (ref "C2") (pin "1") (pinfunction "1_1") (pintype "passive"))
      (node (ref "D1") (pin "2") (pinfunction "A_2") (pintype "passive"))
      (node (ref "IC2") (pin "4") (pinfunction "VDD_4") (pintype "power_in"))
      (node (ref "USB-C") (pin "A4") (pinfunction "VBUS_A4") (pintype "passive"))
      (node (ref "USB-C") (pin "A9") (pinfunction "VBUS1_A9") (pintype "passive"))
      (node (ref "USB-C") (pin "B4") (pinfunction "VBUS2_B4") (pintype "passive"))
      (node (ref "USB-C") (pin "B9") (pinfunction "VBUS3_B9") (pintype "passive"))
    )
    (net (code "47") (name "VOLUME_DOWN") (class "Default")
      (node (ref "IC1") (pin "15") (pinfunction "P1_5_15") (pintype "bidirectional"))
      (node (ref "R25") (pin "1") (pinfunction "1_1") (pintype "passive"))
      (node (ref "S2") (pin "1") (pinfunction "1_1") (pintype "bidirectional"))
      (node (ref "S2") (pin "2") (pinfunction "2_2") (pintype "bidirectional"))
    )
    (net (code "48") (name "VOLUME_UP") (class "Default")
      (node (ref "IC1") (pin "14") (pinfunction "P1_4_14") (pintype "bidirectional"))
      (node (ref "R24") (pin "1") (pinfunction "1_1") (pintype "passive"))
      (node (ref "S1") (pin "1") (pinfunction "1_1") (pintype "bidirectional"))
      (node (ref "S1") (pin "2") (pinfunction "2_2") (pintype "bidirectional"))
    )
    (net (code "49") (name "X") (class "Default")
      (node (ref "IC1") (pin "12") (pinfunction "P0_6_12") (pintype "bidirectional"))
      (node (ref "R1") (pin "1") (pinfunction "1_1") (pintype "passive"))
      (node (ref "X") (pin "P$1") (pinfunction "1_P$1") (pintype "passive"))
      (node (ref "X") (pin "P$3") (pinfunction "1_P$3") (pintype "passive"))
    )
    (net (code "50") (name "Y") (class "Default")
      (node (ref "IC1") (pin "13") (pinfunction "P0_7_13") (pintype "bidirectional"))
      (node (ref "R2") (pin "1") (pinfunction "1_1") (pintype "passive"))
      (node (ref "Y") (pin "P$1") (pinfunction "1_P$1") (pintype "passive"))
      (node (ref "Y") (pin "P$3") (pinfunction "1_P$3") (pintype "passive"))
    )
    (net (code "51") (name "unconnected-(HAPTIC-IN{slash}TRIG-PadP$4)") (class "Default")
      (node (ref "HAPTIC") (pin "P$4") (pinfunction "IN/TRIG_P$4") (pintype "bidirectional"))
    )
    (net (code "52") (name "unconnected-(HAPTIC-REG-PadP$1)") (class "Default")
      (node (ref "HAPTIC") (pin "P$1") (pinfunction "REG_P$1") (pintype "bidirectional"))
    )
    (net (code "53") (name "unconnected-(IC1-P1_2-Pad3)") (class "Default")
      (node (ref "IC1") (pin "3") (pinfunction "P1_2_3") (pintype "bidirectional"))
    )
    (net (code "54") (name "unconnected-(IC1-P1_6-Pad16)") (class "Default")
      (node (ref "IC1") (pin "16") (pinfunction "P1_6_16") (pintype "bidirectional"))
    )
    (net (code "55") (name "unconnected-(IC1-P1_7-Pad17)") (class "Default")
      (node (ref "IC1") (pin "17") (pinfunction "P1_7_17") (pintype "bidirectional"))
    )
    (net (code "56") (name "unconnected-(J2-PadCD1)") (class "Default")
      (node (ref "J2") (pin "CD1") (pinfunction "CD1_CD1") (pintype "bidirectional"))
    )
    (net (code "57") (name "unconnected-(J2-PadCD2)") (class "Default")
      (node (ref "J2") (pin "CD2") (pinfunction "CD2_CD2") (pintype "bidirectional"))
    )
    (net (code "58") (name "unconnected-(J2-RSV-PadRSV1)") (class "Default")
      (node (ref "J2") (pin "RSV1") (pinfunction "RSV_RSV1") (pintype "bidirectional"))
    )
    (net (code "59") (name "unconnected-(J2-RSV-PadRSV2)") (class "Default")
      (node (ref "J2") (pin "RSV2") (pinfunction "RSV_RSV2") (pintype "bidirectional"))
    )
    (net (code "60") (name "unconnected-(USB-C-SBU1-PadA8)") (class "Default")
      (node (ref "USB-C") (pin "A8") (pinfunction "SBU1_A8") (pintype "passive"))
    )
    (net (code "61") (name "unconnected-(USB-C-SBU2-PadB8)") (class "Default")
      (node (ref "USB-C") (pin "B8") (pinfunction "SBU2_B8") (pintype "passive"))
    )
    (net (code "62") (name "~{BAT_ALERT}") (class "Default")
      (node (ref "IC1") (pin "4") (pinfunction "P1_3_4") (pintype "bidirectional"))
      (node (ref "R21") (pin "2") (pinfunction "2_2") (pintype "passive"))
      (node (ref "U1") (pin "5") (pinfunction "~{ALRT}_5") (pintype "output"))
    )
  )
)
